# Seeeduino_Stalker_v3_1.net
KiCad netlist of a schematic drawn in EAGLE
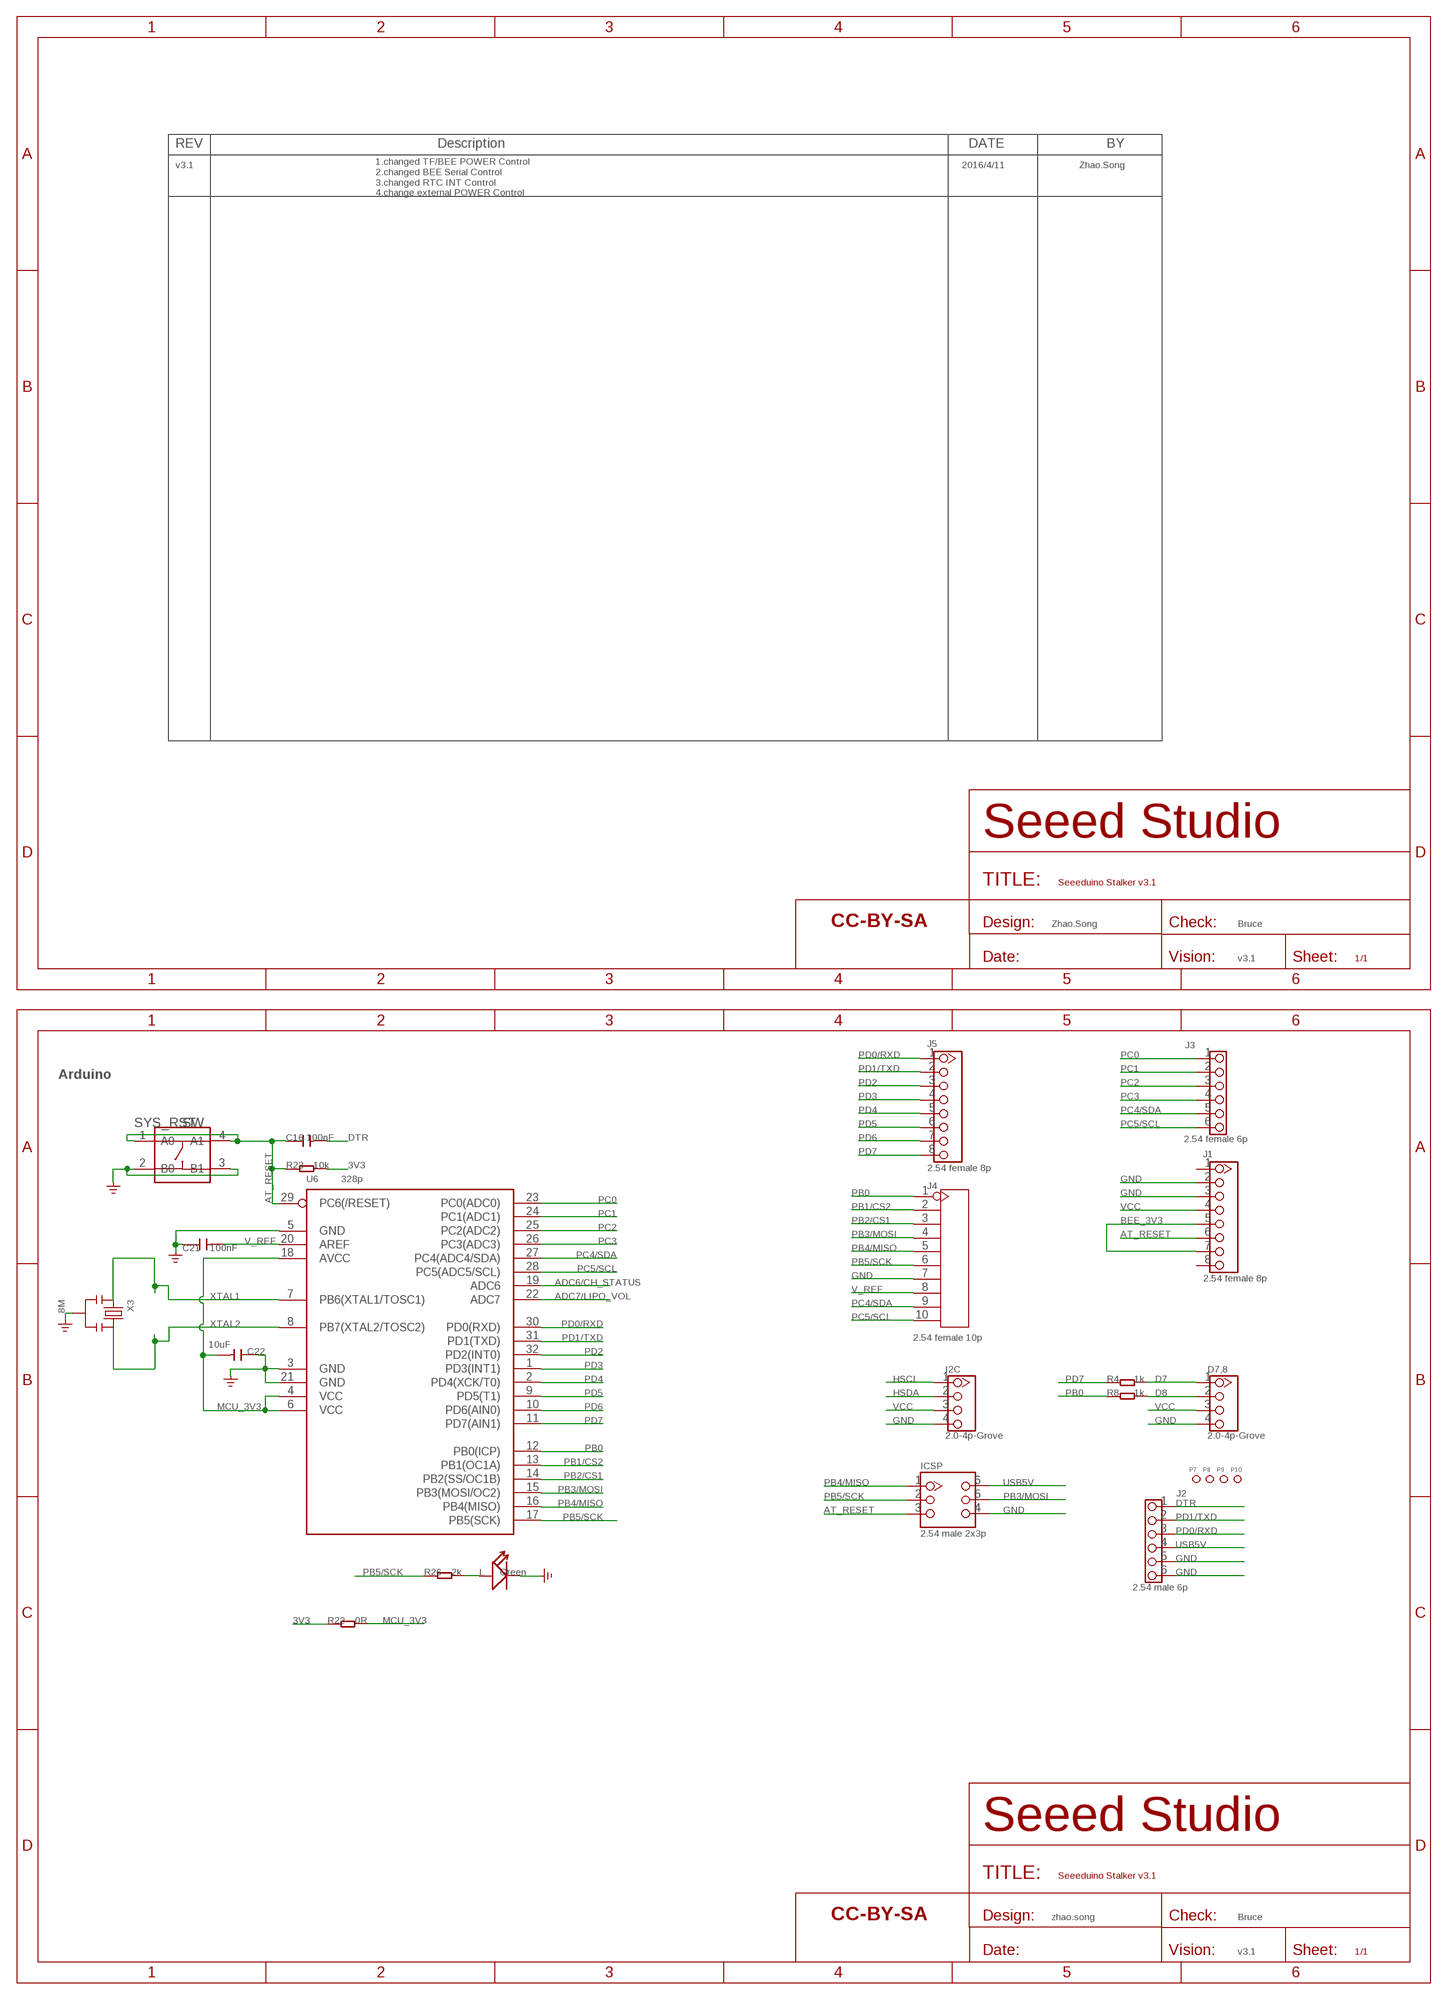
[diagram p0: schematic, sheet 1, part 1 of 2]
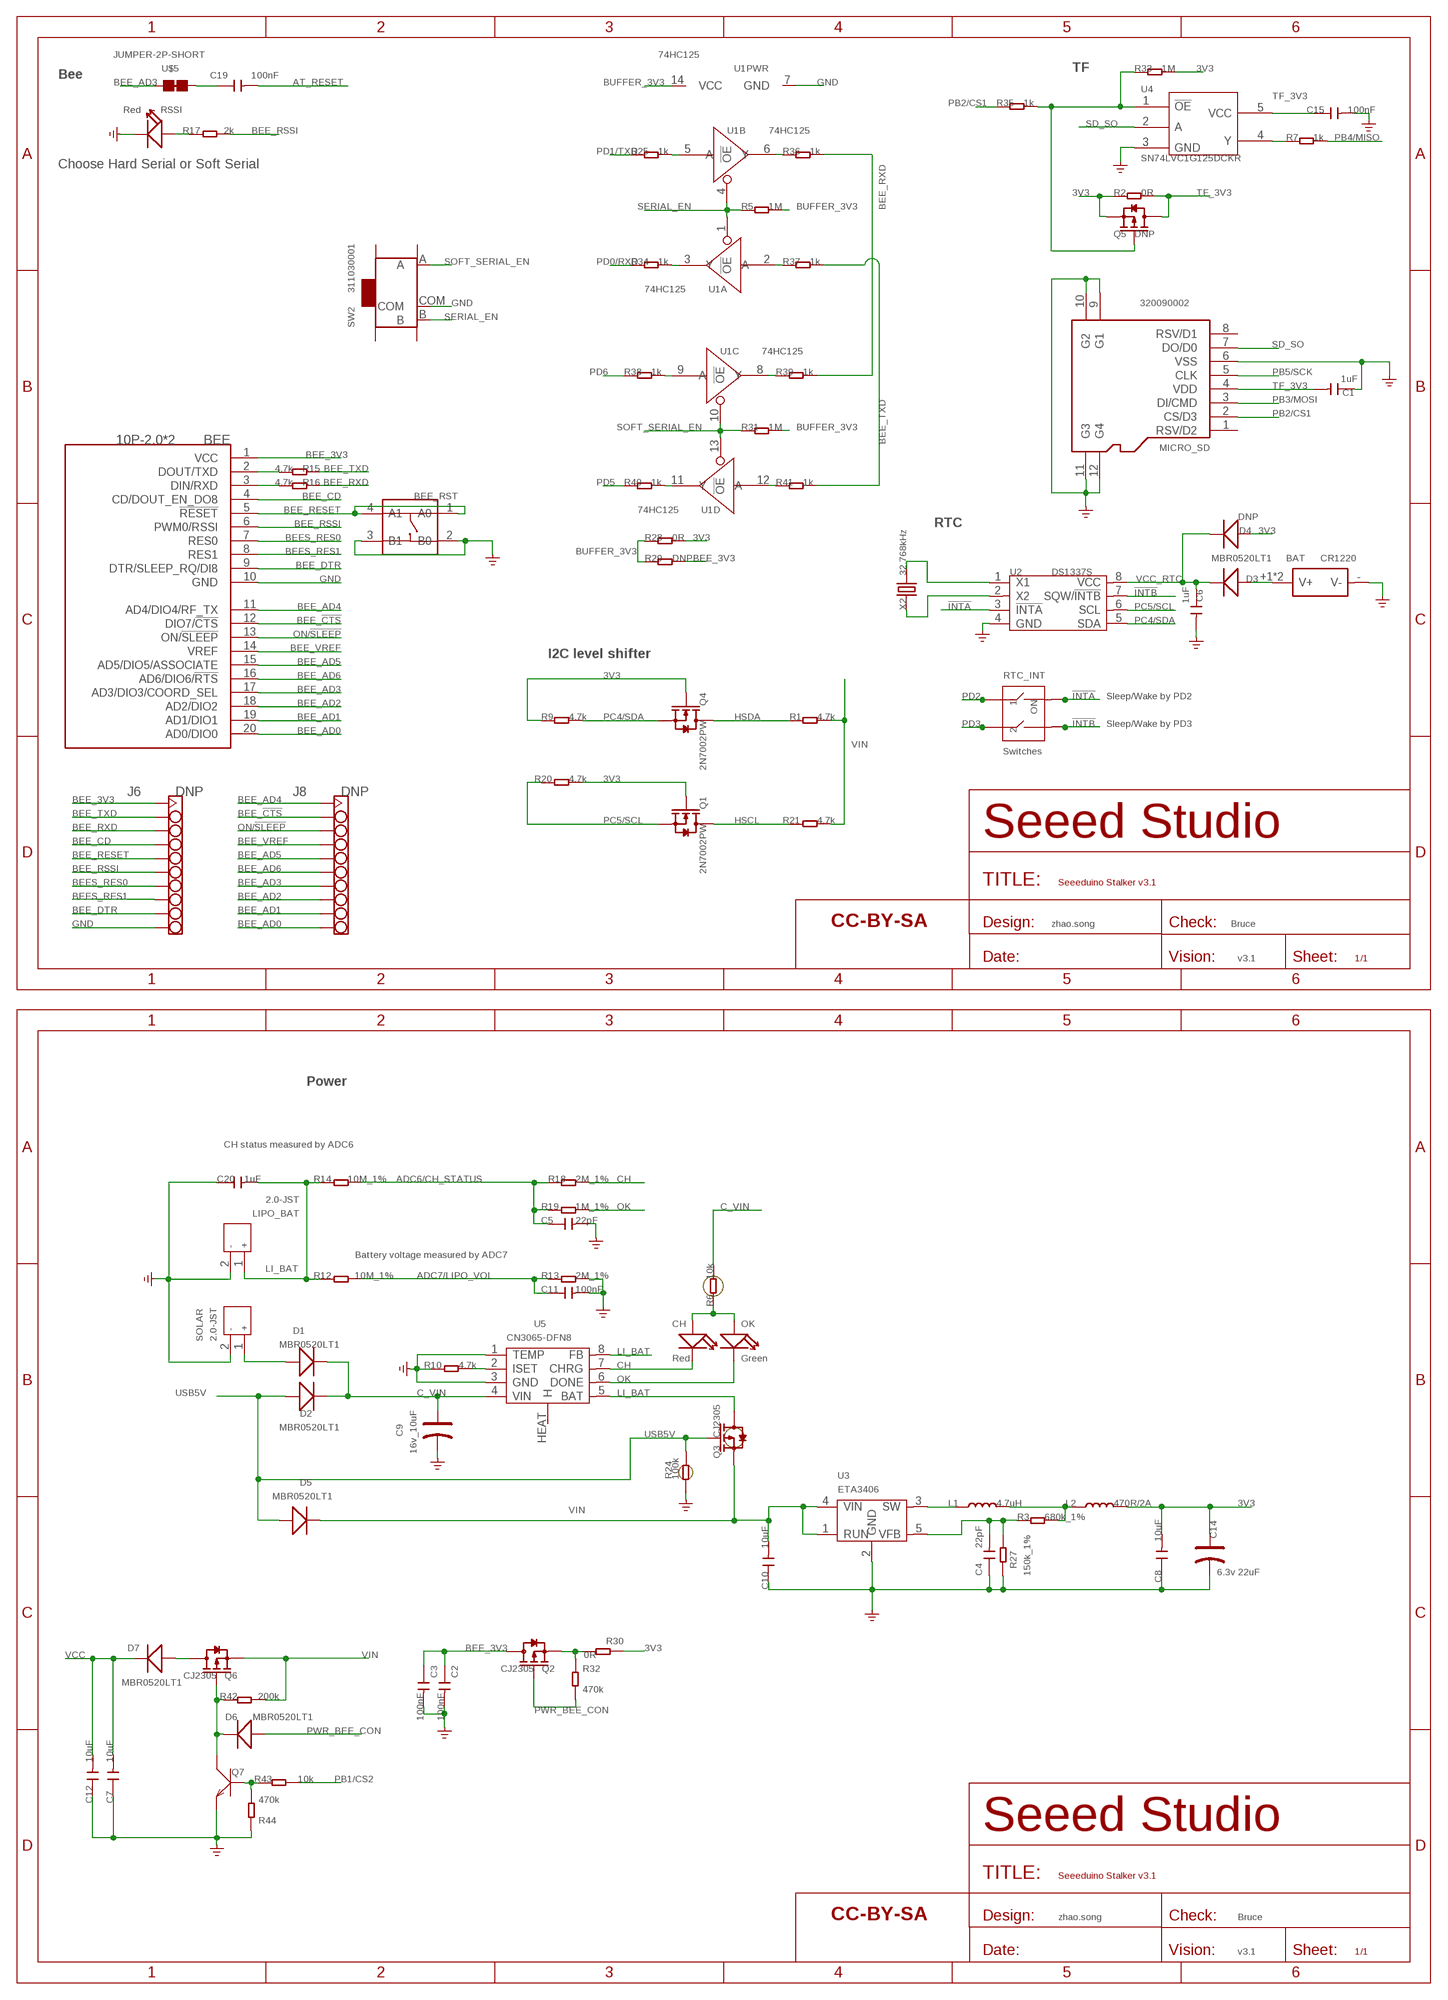
[diagram p1: schematic, sheet 1, part 2 of 2]

(export (version "E")
  (design (tool "Eeschema 10.0.6"))
  (components
    (comp (ref "BAT")
      (value "CR1220")
      (footprint "eagle-import:BAT2P-13.5-CR1220")
      (libsource (lib "eagle-import") (part "BAT-HOLDER-1220"))
    )
    (comp (ref "BEE")
      (value "10P-2.0*2")
      (footprint "eagle-import:BEE")
      (libsource (lib "eagle-import") (part "BEEO"))
    )
    (comp (ref "BEE_RST")
      (value "SW")
      (footprint "eagle-import:4P-SMD-6.2X6.2X4H")
      (libsource (lib "eagle-import") (part "BUTTON-4P-6X6-SMD"))
    )
    (comp (ref "C1")
      (value "1uF")
      (footprint "eagle-import:C0805")
      (libsource (lib "eagle-import") (part "C-0805"))
    )
    (comp (ref "C2")
      (value "100nF")
      (footprint "eagle-import:C0603")
      (libsource (lib "eagle-import") (part "C-0603"))
    )
    (comp (ref "C3")
      (value "100nF")
      (footprint "eagle-import:C0603")
      (libsource (lib "eagle-import") (part "C-0603"))
    )
    (comp (ref "C4")
      (value "22pF")
      (footprint "eagle-import:C0603")
      (libsource (lib "eagle-import") (part "C-0603"))
    )
    (comp (ref "C5")
      (value "22pF")
      (footprint "eagle-import:C0603")
      (libsource (lib "eagle-import") (part "C-0603"))
    )
    (comp (ref "C6")
      (value "1uF")
      (footprint "eagle-import:C0805")
      (libsource (lib "eagle-import") (part "C-0805"))
    )
    (comp (ref "C7")
      (value "10uF")
      (footprint "eagle-import:C0805")
      (libsource (lib "eagle-import") (part "C-0805"))
    )
    (comp (ref "C8")
      (value "10uF")
      (footprint "eagle-import:C0805")
      (libsource (lib "eagle-import") (part "C-0805"))
    )
    (comp (ref "C9")
      (value "16v_10uF")
      (footprint "eagle-import:AVX-A")
      (libsource (lib "eagle-import") (part "CAP-AVX-A"))
    )
    (comp (ref "C10")
      (value "10uF")
      (footprint "eagle-import:C0805")
      (libsource (lib "eagle-import") (part "C-0805"))
    )
    (comp (ref "C11")
      (value "100nF")
      (footprint "eagle-import:C0603")
      (libsource (lib "eagle-import") (part "C-0603"))
    )
    (comp (ref "C12")
      (value "10uF")
      (footprint "eagle-import:C0805")
      (libsource (lib "eagle-import") (part "C-0805"))
    )
    (comp (ref "C14")
      (value "6.3v 22uF")
      (footprint "eagle-import:AVX-A")
      (libsource (lib "eagle-import") (part "CAP-AVX-A"))
    )
    (comp (ref "C15")
      (value "100nF")
      (footprint "eagle-import:C0603")
      (libsource (lib "eagle-import") (part "C-0603"))
    )
    (comp (ref "C16")
      (value "100nF")
      (footprint "eagle-import:C0603")
      (libsource (lib "eagle-import") (part "C-0603"))
    )
    (comp (ref "C19")
      (value "100nF")
      (footprint "eagle-import:C0603")
      (libsource (lib "eagle-import") (part "C-0603"))
    )
    (comp (ref "C20")
      (value "1uF")
      (footprint "eagle-import:C0805")
      (libsource (lib "eagle-import") (part "C-0805"))
    )
    (comp (ref "C21")
      (value "100nF")
      (footprint "eagle-import:C0603")
      (libsource (lib "eagle-import") (part "C-0603"))
    )
    (comp (ref "C22")
      (value "10uF")
      (footprint "eagle-import:C0805")
      (libsource (lib "eagle-import") (part "C-0805"))
    )
    (comp (ref "CH")
      (value "Red")
      (footprint "eagle-import:D0603")
      (libsource (lib "eagle-import") (part "007-LED0603"))
    )
    (comp (ref "D1")
      (value "MBR0520LT1")
      (footprint "eagle-import:SOD123-2.7X1.6")
      (libsource (lib "eagle-import") (part "D'MBR0520LT1'"))
    )
    (comp (ref "D2")
      (value "MBR0520LT1")
      (footprint "eagle-import:SOD123-2.7X1.6")
      (libsource (lib "eagle-import") (part "D'MBR0520LT1'"))
    )
    (comp (ref "D3")
      (value "MBR0520LT1")
      (footprint "eagle-import:SOD123-2.7X1.6")
      (libsource (lib "eagle-import") (part "D'MBR0520LT1'"))
    )
    (comp (ref "D4")
      (value "DNP")
      (footprint "eagle-import:SOD123-2.7X1.6")
      (libsource (lib "eagle-import") (part "D'MBR0520LT1'"))
    )
    (comp (ref "D5")
      (value "MBR0520LT1")
      (footprint "eagle-import:SOD123-2.7X1.6")
      (libsource (lib "eagle-import") (part "D'MBR0520LT1'"))
    )
    (comp (ref "D6")
      (value "MBR0520LT1")
      (footprint "eagle-import:SOD123-2.7X1.6")
      (libsource (lib "eagle-import") (part "D'MBR0520LT1'"))
    )
    (comp (ref "D7")
      (value "MBR0520LT1")
      (footprint "eagle-import:SOD123-2.7X1.6")
      (libsource (lib "eagle-import") (part "D'MBR0520LT1'"))
    )
    (comp (ref "D7,8")
      (value "2.0-4p-Grove")
      (footprint "eagle-import:4P-2.0")
      (libsource (lib "eagle-import") (part "TWIG-4P-2.0-2.0"))
    )
    (comp (ref "I2C")
      (value "2.0-4p-Grove")
      (footprint "eagle-import:4P-2.0")
      (libsource (lib "eagle-import") (part "TWIG-4P-2.0-2.0"))
    )
    (comp (ref "ICSP")
      (value "2.54 male 2x3p")
      (footprint "eagle-import:2X3P-2.54-LEADED")
      (libsource (lib "eagle-import") (part "HEADER-2X3P-2.54"))
    )
    (comp (ref "J1")
      (value "2.54 female 8p")
      (footprint "eagle-import:8P-2.54-LEADED")
      (libsource (lib "eagle-import") (part "HEADER-8P-2.54-LEADED"))
    )
    (comp (ref "J2")
      (value "2.54 male 6p")
      (footprint "eagle-import:6P-2.54-LEADED")
      (libsource (lib "eagle-import") (part "HEADER-6P-LEADED-2.54"))
    )
    (comp (ref "J3")
      (value "2.54 female 6p")
      (footprint "eagle-import:6P-2.54-LEADED")
      (libsource (lib "eagle-import") (part "HEADER-6P-LEADED-2.54"))
    )
    (comp (ref "J4")
      (value "2.54 female 10p")
      (footprint "eagle-import:10P-2.54")
      (libsource (lib "eagle-import") (part "HEADER-10P-2.54"))
    )
    (comp (ref "J5")
      (value "2.54 female 8p")
      (footprint "eagle-import:8P-2.54-LEADED")
      (libsource (lib "eagle-import") (part "HEADER-8P-2.54-LEADED"))
    )
    (comp (ref "J6")
      (value "DNP")
      (footprint "eagle-import:HEADER_1X10")
      (libsource (lib "eagle-import") (part "HEADER_1X10DD"))
    )
    (comp (ref "J8")
      (value "DNP")
      (footprint "eagle-import:HEADER_1X10")
      (libsource (lib "eagle-import") (part "HEADER_1X10DD"))
    )
    (comp (ref "L")
      (value "Green")
      (footprint "eagle-import:D0603")
      (libsource (lib "eagle-import") (part "007-LED0603"))
    )
    (comp (ref "L1")
      (value "4.7uH")
      (footprint "eagle-import:L0420")
      (libsource (lib "eagle-import") (part "LSPD3D16-4R7M"))
    )
    (comp (ref "L2")
      (value "470R/2A")
      (footprint "eagle-import:L0805")
      (libsource (lib "eagle-import") (part "L'0805'"))
    )
    (comp (ref "LIPO_BAT")
      (value "2.0-JST")
      (footprint "eagle-import:JST-2.0")
      (libsource (lib "eagle-import") (part "JACK-JST-2P-PW'2.0'"))
    )
    (comp (ref "MICRO_SD")
      (value "320090002")
      (footprint "eagle-import:MICRO-SD8+4P-SMD-14.5X13.6X1.8MM")
      (libsource (lib "eagle-import") (part "MICRO-SD-CARD-HOLDER-8P"))
    )
    (comp (ref "OK")
      (value "Green")
      (footprint "eagle-import:D0603")
      (libsource (lib "eagle-import") (part "007-LED0603"))
    )
    (comp (ref "P7")
      (value "DNP")
      (footprint "eagle-import:ROUND-MARK-1.0")
      (libsource (lib "eagle-import") (part "PAD-MARK"))
    )
    (comp (ref "P8")
      (value "DNP")
      (footprint "eagle-import:ROUND-MARK-1.0")
      (libsource (lib "eagle-import") (part "PAD-MARK"))
    )
    (comp (ref "P9")
      (value "DNP")
      (footprint "eagle-import:ROUND-MARK-1.0")
      (libsource (lib "eagle-import") (part "PAD-MARK"))
    )
    (comp (ref "P10")
      (value "DNP")
      (footprint "eagle-import:ROUND-MARK-1.0")
      (libsource (lib "eagle-import") (part "PAD-MARK"))
    )
    (comp (ref "Q1")
      (value "2N7002PW")
      (footprint "eagle-import:SOT23")
      (libsource (lib "eagle-import") (part "MOSFET-N'SOT23'"))
    )
    (comp (ref "Q2")
      (value "CJ2305")
      (footprint "eagle-import:SOT23")
      (libsource (lib "eagle-import") (part "MOSFET-P'SI2323CDS/SI2305DS{lt}BR{gt}'"))
    )
    (comp (ref "Q3")
      (value "CJ2305")
      (footprint "eagle-import:SOT23")
      (libsource (lib "eagle-import") (part "MOSFET-P'SI2323CDS/SI2305DS{lt}BR{gt}'"))
    )
    (comp (ref "Q4")
      (value "2N7002PW")
      (footprint "eagle-import:SOT23")
      (libsource (lib "eagle-import") (part "MOSFET-N'SOT23'"))
    )
    (comp (ref "Q5")
      (value "DNP")
      (footprint "eagle-import:SOT23")
      (libsource (lib "eagle-import") (part "MOSFET-P'SI2323CDS/SI2305DS{lt}BR{gt}'"))
    )
    (comp (ref "Q6")
      (value "CJ2305")
      (footprint "eagle-import:SOT23")
      (libsource (lib "eagle-import") (part "MOSFET-P'SI2323CDS/SI2305DS{lt}BR{gt}'"))
    )
    (comp (ref "Q7")
      (value "TRANSISTOR-NPN-SOT23")
      (footprint "eagle-import:SOT-23")
      (libsource (lib "eagle-import") (part "TRANSISTOR-NPN-SOT23"))
    )
    (comp (ref "R1")
      (value "4.7k")
      (footprint "eagle-import:0603@1")
      (libsource (lib "eagle-import") (part "005-R0603"))
    )
    (comp (ref "R2")
      (value "0R")
      (footprint "eagle-import:0603@1")
      (libsource (lib "eagle-import") (part "005-R0603"))
    )
    (comp (ref "R3")
      (value "680k_1%")
      (footprint "eagle-import:0603@1")
      (libsource (lib "eagle-import") (part "005-R0603"))
    )
    (comp (ref "R4")
      (value "1k")
      (footprint "eagle-import:0603@1")
      (libsource (lib "eagle-import") (part "005-R0603"))
    )
    (comp (ref "R5")
      (value "1M")
      (footprint "eagle-import:0603@1")
      (libsource (lib "eagle-import") (part "005-R0603"))
    )
    (comp (ref "R6")
      (value "10k")
      (footprint "eagle-import:0603@1")
      (libsource (lib "eagle-import") (part "005-R0603"))
    )
    (comp (ref "R7")
      (value "1k")
      (footprint "eagle-import:0603@1")
      (libsource (lib "eagle-import") (part "005-R0603"))
    )
    (comp (ref "R8")
      (value "1k")
      (footprint "eagle-import:0603@1")
      (libsource (lib "eagle-import") (part "005-R0603"))
    )
    (comp (ref "R9")
      (value "4.7k")
      (footprint "eagle-import:0603@1")
      (libsource (lib "eagle-import") (part "005-R0603"))
    )
    (comp (ref "R10")
      (value "4.7k")
      (footprint "eagle-import:0603@1")
      (libsource (lib "eagle-import") (part "005-R0603"))
    )
    (comp (ref "R12")
      (value "10M_1%")
      (footprint "eagle-import:0603@1")
      (libsource (lib "eagle-import") (part "005-R0603"))
    )
    (comp (ref "R13")
      (value "2M_1%")
      (footprint "eagle-import:0603@1")
      (libsource (lib "eagle-import") (part "005-R0603"))
    )
    (comp (ref "R14")
      (value "10M_1%")
      (footprint "eagle-import:0603@1")
      (libsource (lib "eagle-import") (part "005-R0603"))
    )
    (comp (ref "R15")
      (value "4.7k")
      (footprint "eagle-import:0603@1")
      (libsource (lib "eagle-import") (part "005-R0603"))
    )
    (comp (ref "R16")
      (value "4.7k")
      (footprint "eagle-import:0603@1")
      (libsource (lib "eagle-import") (part "005-R0603"))
    )
    (comp (ref "R17")
      (value "2k")
      (footprint "eagle-import:0603@1")
      (libsource (lib "eagle-import") (part "005-R0603"))
    )
    (comp (ref "R18")
      (value "2M_1%")
      (footprint "eagle-import:0603@1")
      (libsource (lib "eagle-import") (part "005-R0603"))
    )
    (comp (ref "R19")
      (value "1M_1%")
      (footprint "eagle-import:0603@1")
      (libsource (lib "eagle-import") (part "005-R0603"))
    )
    (comp (ref "R20")
      (value "4.7k")
      (footprint "eagle-import:0603@1")
      (libsource (lib "eagle-import") (part "005-R0603"))
    )
    (comp (ref "R21")
      (value "4.7k")
      (footprint "eagle-import:0603@1")
      (libsource (lib "eagle-import") (part "005-R0603"))
    )
    (comp (ref "R22")
      (value "0R")
      (footprint "eagle-import:0603@1")
      (libsource (lib "eagle-import") (part "005-R0603"))
    )
    (comp (ref "R23")
      (value "10k")
      (footprint "eagle-import:0603@1")
      (libsource (lib "eagle-import") (part "005-R0603"))
    )
    (comp (ref "R24")
      (value "100k")
      (footprint "eagle-import:0603@1")
      (libsource (lib "eagle-import") (part "005-R0603"))
    )
    (comp (ref "R25")
      (value "1k")
      (footprint "eagle-import:0603@1")
      (libsource (lib "eagle-import") (part "005-R0603"))
    )
    (comp (ref "R26")
      (value "2k")
      (footprint "eagle-import:0603@1")
      (libsource (lib "eagle-import") (part "005-R0603"))
    )
    (comp (ref "R27")
      (value "150k_1%")
      (footprint "eagle-import:0603@1")
      (libsource (lib "eagle-import") (part "005-R0603"))
    )
    (comp (ref "R28")
      (value "0R")
      (footprint "eagle-import:0603@1")
      (libsource (lib "eagle-import") (part "005-R0603"))
    )
    (comp (ref "R29")
      (value "DNP")
      (footprint "eagle-import:0603@1")
      (libsource (lib "eagle-import") (part "005-R0603"))
    )
    (comp (ref "R30")
      (value "0R")
      (footprint "eagle-import:0603@1")
      (libsource (lib "eagle-import") (part "005-R0603"))
    )
    (comp (ref "R31")
      (value "1M")
      (footprint "eagle-import:0603@1")
      (libsource (lib "eagle-import") (part "005-R0603"))
    )
    (comp (ref "R32")
      (value "470k")
      (footprint "eagle-import:0603@1")
      (libsource (lib "eagle-import") (part "005-R0603"))
    )
    (comp (ref "R33")
      (value "1M")
      (footprint "eagle-import:0603@1")
      (libsource (lib "eagle-import") (part "005-R0603"))
    )
    (comp (ref "R34")
      (value "1k")
      (footprint "eagle-import:0603@1")
      (libsource (lib "eagle-import") (part "005-R0603"))
    )
    (comp (ref "R35")
      (value "1k")
      (footprint "eagle-import:0603@1")
      (libsource (lib "eagle-import") (part "005-R0603"))
    )
    (comp (ref "R36")
      (value "1k")
      (footprint "eagle-import:0603@1")
      (libsource (lib "eagle-import") (part "005-R0603"))
    )
    (comp (ref "R37")
      (value "1k")
      (footprint "eagle-import:0603@1")
      (libsource (lib "eagle-import") (part "005-R0603"))
    )
    (comp (ref "R38")
      (value "1k")
      (footprint "eagle-import:0603@1")
      (libsource (lib "eagle-import") (part "005-R0603"))
    )
    (comp (ref "R39")
      (value "1k")
      (footprint "eagle-import:0603@1")
      (libsource (lib "eagle-import") (part "005-R0603"))
    )
    (comp (ref "R40")
      (value "1k")
      (footprint "eagle-import:0603@1")
      (libsource (lib "eagle-import") (part "005-R0603"))
    )
    (comp (ref "R41")
      (value "1k")
      (footprint "eagle-import:0603@1")
      (libsource (lib "eagle-import") (part "005-R0603"))
    )
    (comp (ref "R42")
      (value "200k")
      (footprint "eagle-import:0603@1")
      (libsource (lib "eagle-import") (part "005-R0603"))
    )
    (comp (ref "R43")
      (value "10k")
      (footprint "eagle-import:0603@1")
      (libsource (lib "eagle-import") (part "005-R0603"))
    )
    (comp (ref "R44")
      (value "470k")
      (footprint "eagle-import:0603@1")
      (libsource (lib "eagle-import") (part "005-R0603"))
    )
    (comp (ref "RSSI")
      (value "Red")
      (footprint "eagle-import:D0603")
      (libsource (lib "eagle-import") (part "007-LED0603"))
    )
    (comp (ref "RTC_INT")
      (value "Switches")
      (footprint "eagle-import:SW4-SMD-2.54-5.08X6.8X3.3MM")
      (libsource (lib "eagle-import") (part "SWITCHES-2X2P'KM-02'"))
    )
    (comp (ref "SOLAR")
      (value "2.0-JST")
      (footprint "eagle-import:JST-2.0")
      (libsource (lib "eagle-import") (part "JACK-JST-2P-PW'2.0'"))
    )
    (comp (ref "SW2")
      (value "311030001")
      (footprint "eagle-import:SW7-SMD-L6.7X2.7X3.2MM")
      (libsource (lib "eagle-import") (part "SWITCH-3+4P"))
    )
    (comp (ref "SYS_RST")
      (value "SW")
      (footprint "eagle-import:4P-SMD-6.2X6.2X4H")
      (libsource (lib "eagle-import") (part "BUTTON-4P-6X6-SMD"))
    )
    (comp (ref "U$2")
      (value "DNP")
      (footprint "eagle-import:SEEEDSTUDIO-PCB-FRAME")
      (libsource (lib "eagle-import") (part "SEEEDSTUDIO-OPEN-SCH-FRAME"))
    )
    (comp (ref "U$5")
      (value "JUMPER-2P-SHORT")
      (footprint "eagle-import:2P-SMD-SHORT")
      (libsource (lib "eagle-import") (part "JUMPER-2P-SHORT"))
    )
    (comp (ref "U$11")
      (value "DNP")
      (footprint "eagle-import:SEEEDSTUDIO-PCB-FRAME")
      (libsource (lib "eagle-import") (part "SEEEDSTUDIO-OPEN-SCH-FRAME"))
    )
    (comp (ref "U$12")
      (value "DNP")
      (footprint "eagle-import:SEEEDSTUDIO-PCB-FRAME")
      (libsource (lib "eagle-import") (part "SEEEDSTUDIO-OPEN-SCH-FRAME"))
    )
    (comp (ref "U$27")
      (value "DNP")
      (footprint "eagle-import:SEEEDSTUDIO-PCB-FRAME")
      (libsource (lib "eagle-import") (part "SEEEDSTUDIO-OPEN-SCH-FRAME"))
    )
    (comp (ref "U1")
      (value "74HC125")
      (footprint "eagle-import:TSSOP14-0.65-5X4.4MM")
      (libsource (lib "eagle-import") (part "LOGIC-74125PWHCT"))
    )
    (comp (ref "U2")
      (value "DS1337S")
      (footprint "eagle-import:SOP8")
      (libsource (lib "eagle-import") (part "DS1337S"))
    )
    (comp (ref "U3")
      (value "ETA3406")
      (footprint "eagle-import:SOT23-5")
      (libsource (lib "eagle-import") (part "TD6810'TSOT23-5'"))
    )
    (comp (ref "U4")
      (value "SN74LVC1G125DCKR")
      (footprint "eagle-import:SOT353")
      (libsource (lib "eagle-import") (part "SN74LVC1G125DCKR"))
    )
    (comp (ref "U5")
      (value "CN3065-DFN8")
      (footprint "eagle-import:DFN8")
      (libsource (lib "eagle-import") (part "CN3065-DFN8"))
    )
    (comp (ref "U6")
      (value "328p")
      (footprint "eagle-import:TQFP32-0.8-7X7MM")
      (libsource (lib "eagle-import") (part "MCU-ATMEGA8/168/328'AU'"))
    )
    (comp (ref "X2")
      (value "32.768kHz")
      (footprint "eagle-import:2P-SMD-3.2X1.5")
      (libsource (lib "eagle-import") (part "CRYSTAL-3215"))
    )
    (comp (ref "X3")
      (value "8M")
      (footprint "eagle-import:RESONATOR3-SMD-3.6X1.3X0.8MM")
      (libsource (lib "eagle-import") (part "CRYSTAL-RESONATOR'SMD'"))
    )
  )
  (nets
    (net (code "1") (name "/3V3") (class "Default")
      (node (ref "C14") (pin "+") (pinfunction "+_+") (pintype "passive"))
      (node (ref "C8") (pin "2") (pinfunction "2_2") (pintype "passive"))
      (node (ref "D4") (pin "1") (pinfunction "+_1") (pintype "passive"))
      (node (ref "L2") (pin "2") (pinfunction "2_2") (pintype "passive"))
      (node (ref "Q1") (pin "1") (pinfunction "G_1") (pintype "passive"))
      (node (ref "Q4") (pin "1") (pinfunction "G_1") (pintype "passive"))
      (node (ref "Q5") (pin "2") (pinfunction "S_2") (pintype "passive"))
      (node (ref "R2") (pin "1") (pinfunction "1_1") (pintype "passive"))
      (node (ref "R20") (pin "2") (pinfunction "2_2") (pintype "passive"))
      (node (ref "R22") (pin "1") (pinfunction "1_1") (pintype "passive"))
      (node (ref "R23") (pin "2") (pinfunction "2_2") (pintype "passive"))
      (node (ref "R28") (pin "2") (pinfunction "2_2") (pintype "passive"))
      (node (ref "R30") (pin "1") (pinfunction "1_1") (pintype "passive"))
      (node (ref "R33") (pin "2") (pinfunction "2_2") (pintype "passive"))
      (node (ref "R9") (pin "1") (pinfunction "1_1") (pintype "passive"))
    )
    (net (code "2") (name "/ADC6{slash}CH_STATUS") (class "Default")
      (node (ref "C5") (pin "1") (pinfunction "1_1") (pintype "passive"))
      (node (ref "R14") (pin "2") (pinfunction "2_2") (pintype "passive"))
      (node (ref "R18") (pin "1") (pinfunction "1_1") (pintype "passive"))
      (node (ref "R19") (pin "1") (pinfunction "1_1") (pintype "passive"))
      (node (ref "U6") (pin "19") (pinfunction "ADC6_19") (pintype "bidirectional"))
    )
    (net (code "3") (name "/ADC7{slash}LIPO_VOL") (class "Default")
      (node (ref "C11") (pin "1") (pinfunction "1_1") (pintype "passive"))
      (node (ref "R12") (pin "2") (pinfunction "2_2") (pintype "passive"))
      (node (ref "R13") (pin "1") (pinfunction "1_1") (pintype "passive"))
      (node (ref "U6") (pin "22") (pinfunction "ADC7_22") (pintype "bidirectional"))
    )
    (net (code "4") (name "/AT_RESET") (class "Default")
      (node (ref "C16") (pin "1") (pinfunction "1_1") (pintype "passive"))
      (node (ref "C19") (pin "2") (pinfunction "2_2") (pintype "passive"))
      (node (ref "ICSP") (pin "3") (pinfunction "3_3") (pintype "bidirectional"))
      (node (ref "J1") (pin "6") (pinfunction "6_6") (pintype "bidirectional"))
      (node (ref "R23") (pin "1") (pinfunction "1_1") (pintype "passive"))
      (node (ref "SYS_RST") (pin "1") (pinfunction "A0_1") (pintype "bidirectional"))
      (node (ref "SYS_RST") (pin "4") (pinfunction "A1_4") (pintype "bidirectional"))
      (node (ref "U6") (pin "29") (pinfunction "PC6(/RESET)_29") (pintype "bidirectional"))
    )
    (net (code "5") (name "/BEES_RES0") (class "Default")
      (node (ref "BEE") (pin "7") (pinfunction "RES0_7") (pintype "bidirectional"))
      (node (ref "J6") (pin "7") (pinfunction "7_7") (pintype "bidirectional"))
    )
    (net (code "6") (name "/BEES_RES1") (class "Default")
      (node (ref "BEE") (pin "8") (pinfunction "RES1_8") (pintype "bidirectional"))
      (node (ref "J6") (pin "8") (pinfunction "8_8") (pintype "bidirectional"))
    )
    (net (code "7") (name "/BEE_3V3") (class "Default")
      (node (ref "BEE") (pin "1") (pinfunction "VCC_1") (pintype "bidirectional"))
      (node (ref "C2") (pin "1") (pinfunction "1_1") (pintype "passive"))
      (node (ref "C3") (pin "1") (pinfunction "1_1") (pintype "passive"))
      (node (ref "J1") (pin "5") (pinfunction "5_5") (pintype "bidirectional"))
      (node (ref "J1") (pin "7") (pinfunction "7_7") (pintype "bidirectional"))
      (node (ref "J6") (pin "1") (pinfunction "1_1") (pintype "bidirectional"))
      (node (ref "Q2") (pin "3") (pinfunction "D_3") (pintype "passive"))
      (node (ref "R29") (pin "2") (pinfunction "2_2") (pintype "passive"))
    )
    (net (code "8") (name "/BEE_AD0") (class "Default")
      (node (ref "BEE") (pin "20") (pinfunction "AD0/DIO0_20") (pintype "bidirectional"))
      (node (ref "J8") (pin "10") (pinfunction "10_10") (pintype "bidirectional"))
    )
    (net (code "9") (name "/BEE_AD1") (class "Default")
      (node (ref "BEE") (pin "19") (pinfunction "AD1/DIO1_19") (pintype "bidirectional"))
      (node (ref "J8") (pin "9") (pinfunction "9_9") (pintype "bidirectional"))
    )
    (net (code "10") (name "/BEE_AD2") (class "Default")
      (node (ref "BEE") (pin "18") (pinfunction "AD2/DIO2_18") (pintype "bidirectional"))
      (node (ref "J8") (pin "8") (pinfunction "8_8") (pintype "bidirectional"))
    )
    (net (code "11") (name "/BEE_AD3") (class "Default")
      (node (ref "BEE") (pin "17") (pinfunction "AD3/DIO3/COORD_SEL_17") (pintype "bidirectional"))
      (node (ref "J8") (pin "7") (pinfunction "7_7") (pintype "bidirectional"))
      (node (ref "U$5") (pin "1") (pinfunction "1_1") (pintype "bidirectional"))
    )
    (net (code "12") (name "/BEE_AD4") (class "Default")
      (node (ref "BEE") (pin "11") (pinfunction "AD4/DIO4/RF_TX_11") (pintype "bidirectional"))
      (node (ref "J8") (pin "1") (pinfunction "1_1") (pintype "bidirectional"))
    )
    (net (code "13") (name "/BEE_AD5") (class "Default")
      (node (ref "BEE") (pin "15") (pinfunction "AD5/DIO5/ASSOCIATE_15") (pintype "bidirectional"))
      (node (ref "J8") (pin "5") (pinfunction "5_5") (pintype "bidirectional"))
    )
    (net (code "14") (name "/BEE_AD6") (class "Default")
      (node (ref "BEE") (pin "16") (pinfunction "AD6/DIO6/~{RTS}_16") (pintype "bidirectional"))
      (node (ref "J8") (pin "6") (pinfunction "6_6") (pintype "bidirectional"))
    )
    (net (code "15") (name "/BEE_CD") (class "Default")
      (node (ref "BEE") (pin "4") (pinfunction "CD/DOUT_EN_DO8_4") (pintype "bidirectional"))
      (node (ref "J6") (pin "4") (pinfunction "4_4") (pintype "bidirectional"))
    )
    (net (code "16") (name "/BEE_DTR") (class "Default")
      (node (ref "BEE") (pin "9") (pinfunction "DTR/SLEEP_RQ/DI8_9") (pintype "bidirectional"))
      (node (ref "J6") (pin "9") (pinfunction "9_9") (pintype "bidirectional"))
    )
    (net (code "17") (name "/BEE_RESET") (class "Default")
      (node (ref "BEE") (pin "5") (pinfunction "~{RESET}_5") (pintype "bidirectional"))
      (node (ref "BEE_RST") (pin "1") (pinfunction "A0_1") (pintype "bidirectional"))
      (node (ref "BEE_RST") (pin "4") (pinfunction "A1_4") (pintype "bidirectional"))
      (node (ref "J6") (pin "5") (pinfunction "5_5") (pintype "bidirectional"))
    )
    (net (code "18") (name "/BEE_RSSI") (class "Default")
      (node (ref "BEE") (pin "6") (pinfunction "PWM0/RSSI_6") (pintype "bidirectional"))
      (node (ref "J6") (pin "6") (pinfunction "6_6") (pintype "bidirectional"))
      (node (ref "R17") (pin "2") (pinfunction "2_2") (pintype "passive"))
    )
    (net (code "19") (name "/BEE_RXD") (class "Default")
      (node (ref "J6") (pin "3") (pinfunction "3_3") (pintype "bidirectional"))
      (node (ref "R16") (pin "1") (pinfunction "1_1") (pintype "passive"))
      (node (ref "R36") (pin "2") (pinfunction "2_2") (pintype "passive"))
      (node (ref "R39") (pin "2") (pinfunction "2_2") (pintype "passive"))
    )
    (net (code "20") (name "/BEE_TXD") (class "Default")
      (node (ref "J6") (pin "2") (pinfunction "2_2") (pintype "bidirectional"))
      (node (ref "R15") (pin "1") (pinfunction "1_1") (pintype "passive"))
      (node (ref "R37") (pin "2") (pinfunction "2_2") (pintype "passive"))
      (node (ref "R41") (pin "2") (pinfunction "2_2") (pintype "passive"))
    )
    (net (code "21") (name "/BEE_VREF") (class "Default")
      (node (ref "BEE") (pin "14") (pinfunction "VREF_14") (pintype "bidirectional"))
      (node (ref "J8") (pin "4") (pinfunction "4_4") (pintype "bidirectional"))
    )
    (net (code "22") (name "/BEE_~{CTS}") (class "Default")
      (node (ref "BEE") (pin "12") (pinfunction "DIO7/~{CTS}_12") (pintype "bidirectional"))
      (node (ref "J8") (pin "2") (pinfunction "2_2") (pintype "bidirectional"))
    )
    (net (code "23") (name "/BUFFER_3V3") (class "Default")
      (node (ref "R28") (pin "1") (pinfunction "1_1") (pintype "passive"))
      (node (ref "R29") (pin "1") (pinfunction "1_1") (pintype "passive"))
      (node (ref "R31") (pin "2") (pinfunction "2_2") (pintype "passive"))
      (node (ref "R5") (pin "2") (pinfunction "2_2") (pintype "passive"))
      (node (ref "U1") (pin "14") (pinfunction "VCC_14") (pintype "power_in"))
    )
    (net (code "24") (name "/CH") (class "Default")
      (node (ref "CH") (pin "-") (pinfunction "-_-") (pintype "passive"))
      (node (ref "R18") (pin "2") (pinfunction "2_2") (pintype "passive"))
      (node (ref "U5") (pin "7") (pinfunction "CHRG_7") (pintype "bidirectional"))
    )
    (net (code "25") (name "/C_VIN") (class "Default")
      (node (ref "C9") (pin "+") (pinfunction "+_+") (pintype "passive"))
      (node (ref "D1") (pin "2") (pinfunction "-_2") (pintype "passive"))
      (node (ref "D2") (pin "2") (pinfunction "-_2") (pintype "passive"))
      (node (ref "R6") (pin "2") (pinfunction "2_2") (pintype "passive"))
      (node (ref "U5") (pin "4") (pinfunction "VIN_4") (pintype "input"))
    )
    (net (code "26") (name "/D7") (class "Default")
      (node (ref "D7,8") (pin "1") (pinfunction "1_1") (pintype "bidirectional"))
      (node (ref "R4") (pin "2") (pinfunction "2_2") (pintype "passive"))
    )
    (net (code "27") (name "/D8") (class "Default")
      (node (ref "D7,8") (pin "2") (pinfunction "2_2") (pintype "bidirectional"))
      (node (ref "R8") (pin "2") (pinfunction "2_2") (pintype "passive"))
    )
    (net (code "28") (name "/DTR") (class "Default")
      (node (ref "C16") (pin "2") (pinfunction "2_2") (pintype "passive"))
      (node (ref "J2") (pin "1") (pinfunction "1_1") (pintype "bidirectional"))
    )
    (net (code "29") (name "/HSCL") (class "Default")
      (node (ref "I2C") (pin "1") (pinfunction "1_1") (pintype "bidirectional"))
      (node (ref "Q1") (pin "3") (pinfunction "D_3") (pintype "passive"))
      (node (ref "R21") (pin "1") (pinfunction "1_1") (pintype "passive"))
    )
    (net (code "30") (name "/HSDA") (class "Default")
      (node (ref "I2C") (pin "2") (pinfunction "2_2") (pintype "bidirectional"))
      (node (ref "Q4") (pin "3") (pinfunction "D_3") (pintype "passive"))
      (node (ref "R1") (pin "1") (pinfunction "1_1") (pintype "passive"))
    )
    (net (code "31") (name "/LI_BAT") (class "Default")
      (node (ref "C20") (pin "2") (pinfunction "2_2") (pintype "passive"))
      (node (ref "LIPO_BAT") (pin "1") (pinfunction "P$1_1") (pintype "bidirectional"))
      (node (ref "Q3") (pin "3") (pinfunction "D_3") (pintype "passive"))
      (node (ref "R12") (pin "1") (pinfunction "1_1") (pintype "passive"))
      (node (ref "R14") (pin "1") (pinfunction "1_1") (pintype "passive"))
      (node (ref "U5") (pin "5") (pinfunction "BAT_5") (pintype "bidirectional"))
      (node (ref "U5") (pin "8") (pinfunction "FB_8") (pintype "input"))
    )
    (net (code "32") (name "/MCU_3V3") (class "Default")
      (node (ref "C22") (pin "2") (pinfunction "2_2") (pintype "passive"))
      (node (ref "R22") (pin "2") (pinfunction "2_2") (pintype "passive"))
      (node (ref "U6") (pin "18") (pinfunction "AVCC_18") (pintype "bidirectional"))
      (node (ref "U6") (pin "4") (pinfunction "VCC_4") (pintype "bidirectional"))
      (node (ref "U6") (pin "6") (pinfunction "VCC_6") (pintype "bidirectional"))
    )
    (net (code "33") (name "/OK") (class "Default")
      (node (ref "OK") (pin "-") (pinfunction "-_-") (pintype "passive"))
      (node (ref "R19") (pin "2") (pinfunction "2_2") (pintype "passive"))
      (node (ref "U5") (pin "6") (pinfunction "DONE_6") (pintype "bidirectional"))
    )
    (net (code "34") (name "/ON{slash}~{SLEEP}") (class "Default")
      (node (ref "BEE") (pin "13") (pinfunction "ON/~{SLEEP}_13") (pintype "bidirectional"))
      (node (ref "J8") (pin "3") (pinfunction "3_3") (pintype "bidirectional"))
    )
    (net (code "35") (name "/PB0") (class "Default")
      (node (ref "J4") (pin "1") (pinfunction "1_1") (pintype "bidirectional"))
      (node (ref "R8") (pin "1") (pinfunction "1_1") (pintype "passive"))
      (node (ref "U6") (pin "12") (pinfunction "PB0(ICP)_12") (pintype "bidirectional"))
    )
    (net (code "36") (name "/PB1{slash}CS2") (class "Default")
      (node (ref "J4") (pin "2") (pinfunction "2_2") (pintype "bidirectional"))
      (node (ref "R43") (pin "1") (pinfunction "1_1") (pintype "passive"))
      (node (ref "U6") (pin "13") (pinfunction "PB1(OC1A)_13") (pintype "bidirectional"))
    )
    (net (code "37") (name "/PB2{slash}CS1") (class "Default")
      (node (ref "J4") (pin "3") (pinfunction "3_3") (pintype "bidirectional"))
      (node (ref "MICRO_SD") (pin "2") (pinfunction "CS/D3_2") (pintype "bidirectional"))
      (node (ref "R35") (pin "1") (pinfunction "1_1") (pintype "passive"))
      (node (ref "U6") (pin "14") (pinfunction "PB2(SS/OC1B)_14") (pintype "bidirectional"))
    )
    (net (code "38") (name "/PB3{slash}MOSI") (class "Default")
      (node (ref "ICSP") (pin "5") (pinfunction "5_5") (pintype "bidirectional"))
      (node (ref "J4") (pin "4") (pinfunction "4_4") (pintype "bidirectional"))
      (node (ref "MICRO_SD") (pin "3") (pinfunction "DI/CMD_3") (pintype "bidirectional"))
      (node (ref "U6") (pin "15") (pinfunction "PB3(MOSI/OC2)_15") (pintype "bidirectional"))
    )
    (net (code "39") (name "/PB4{slash}MISO") (class "Default")
      (node (ref "ICSP") (pin "1") (pinfunction "1_1") (pintype "bidirectional"))
      (node (ref "J4") (pin "5") (pinfunction "5_5") (pintype "bidirectional"))
      (node (ref "R7") (pin "2") (pinfunction "2_2") (pintype "passive"))
      (node (ref "U6") (pin "16") (pinfunction "PB4(MISO)_16") (pintype "bidirectional"))
    )
    (net (code "40") (name "/PB5{slash}SCK") (class "Default")
      (node (ref "ICSP") (pin "2") (pinfunction "2_2") (pintype "bidirectional"))
      (node (ref "J4") (pin "6") (pinfunction "6_6") (pintype "bidirectional"))
      (node (ref "MICRO_SD") (pin "5") (pinfunction "CLK_5") (pintype "bidirectional"))
      (node (ref "R26") (pin "1") (pinfunction "1_1") (pintype "passive"))
      (node (ref "U6") (pin "17") (pinfunction "PB5(SCK)_17") (pintype "bidirectional"))
    )
    (net (code "41") (name "/PC0") (class "Default")
      (node (ref "J3") (pin "1") (pinfunction "1_1") (pintype "bidirectional"))
      (node (ref "U6") (pin "23") (pinfunction "PC0(ADC0)_23") (pintype "bidirectional"))
    )
    (net (code "42") (name "/PC1") (class "Default")
      (node (ref "J3") (pin "2") (pinfunction "2_2") (pintype "bidirectional"))
      (node (ref "U6") (pin "24") (pinfunction "PC1(ADC1)_24") (pintype "bidirectional"))
    )
    (net (code "43") (name "/PC2") (class "Default")
      (node (ref "J3") (pin "3") (pinfunction "3_3") (pintype "bidirectional"))
      (node (ref "U6") (pin "25") (pinfunction "PC2(ADC2)_25") (pintype "bidirectional"))
    )
    (net (code "44") (name "/PC3") (class "Default")
      (node (ref "J3") (pin "4") (pinfunction "4_4") (pintype "bidirectional"))
      (node (ref "U6") (pin "26") (pinfunction "PC3(ADC3)_26") (pintype "bidirectional"))
    )
    (net (code "45") (name "/PC4{slash}SDA") (class "Default")
      (node (ref "J3") (pin "5") (pinfunction "5_5") (pintype "bidirectional"))
      (node (ref "J4") (pin "9") (pinfunction "9_9") (pintype "bidirectional"))
      (node (ref "Q4") (pin "2") (pinfunction "S_2") (pintype "passive"))
      (node (ref "R9") (pin "2") (pinfunction "2_2") (pintype "passive"))
      (node (ref "U2") (pin "5") (pinfunction "SDA_5") (pintype "bidirectional"))
      (node (ref "U6") (pin "27") (pinfunction "PC4(ADC4/SDA)_27") (pintype "bidirectional"))
    )
    (net (code "46") (name "/PC5{slash}SCL") (class "Default")
      (node (ref "J3") (pin "6") (pinfunction "6_6") (pintype "bidirectional"))
      (node (ref "J4") (pin "10") (pinfunction "10_10") (pintype "bidirectional"))
      (node (ref "Q1") (pin "2") (pinfunction "S_2") (pintype "passive"))
      (node (ref "R20") (pin "1") (pinfunction "1_1") (pintype "passive"))
      (node (ref "U2") (pin "6") (pinfunction "SCL_6") (pintype "bidirectional"))
      (node (ref "U6") (pin "28") (pinfunction "PC5(ADC5/SCL)_28") (pintype "bidirectional"))
    )
    (net (code "47") (name "/PD0{slash}RXD") (class "Default")
      (node (ref "J2") (pin "3") (pinfunction "3_3") (pintype "bidirectional"))
      (node (ref "J5") (pin "1") (pinfunction "1_1") (pintype "bidirectional"))
      (node (ref "R34") (pin "1") (pinfunction "1_1") (pintype "passive"))
      (node (ref "U6") (pin "30") (pinfunction "PD0(RXD)_30") (pintype "bidirectional"))
    )
    (net (code "48") (name "/PD1{slash}TXD") (class "Default")
      (node (ref "J2") (pin "2") (pinfunction "2_2") (pintype "bidirectional"))
      (node (ref "J5") (pin "2") (pinfunction "2_2") (pintype "bidirectional"))
      (node (ref "R25") (pin "1") (pinfunction "1_1") (pintype "passive"))
      (node (ref "U6") (pin "31") (pinfunction "PD1(TXD)_31") (pintype "bidirectional"))
    )
    (net (code "49") (name "/PD2") (class "Default")
      (node (ref "J5") (pin "3") (pinfunction "3_3") (pintype "bidirectional"))
      (node (ref "RTC_INT") (pin "1") (pinfunction "1_1") (pintype "bidirectional"))
      (node (ref "U6") (pin "32") (pinfunction "PD2(INT0)_32") (pintype "bidirectional"))
    )
    (net (code "50") (name "/PD3") (class "Default")
      (node (ref "J5") (pin "4") (pinfunction "4_4") (pintype "bidirectional"))
      (node (ref "RTC_INT") (pin "2") (pinfunction "2_2") (pintype "bidirectional"))
      (node (ref "U6") (pin "1") (pinfunction "PD3(INT1)_1") (pintype "bidirectional"))
    )
    (net (code "51") (name "/PD4") (class "Default")
      (node (ref "J5") (pin "5") (pinfunction "5_5") (pintype "bidirectional"))
      (node (ref "U6") (pin "2") (pinfunction "PD4(XCK/T0)_2") (pintype "bidirectional"))
    )
    (net (code "52") (name "/PD5") (class "Default")
      (node (ref "J5") (pin "6") (pinfunction "6_6") (pintype "bidirectional"))
      (node (ref "R40") (pin "1") (pinfunction "1_1") (pintype "passive"))
      (node (ref "U6") (pin "9") (pinfunction "PD5(T1)_9") (pintype "bidirectional"))
    )
    (net (code "53") (name "/PD6") (class "Default")
      (node (ref "J5") (pin "7") (pinfunction "7_7") (pintype "bidirectional"))
      (node (ref "R38") (pin "1") (pinfunction "1_1") (pintype "passive"))
      (node (ref "U6") (pin "10") (pinfunction "PD6(AIN0)_10") (pintype "bidirectional"))
    )
    (net (code "54") (name "/PD7") (class "Default")
      (node (ref "J5") (pin "8") (pinfunction "8_8") (pintype "bidirectional"))
      (node (ref "R4") (pin "1") (pinfunction "1_1") (pintype "passive"))
      (node (ref "U6") (pin "11") (pinfunction "PD7(AIN1)_11") (pintype "bidirectional"))
    )
    (net (code "55") (name "/PWR_BEE_CON") (class "Default")
      (node (ref "D6") (pin "1") (pinfunction "+_1") (pintype "passive"))
      (node (ref "Q2") (pin "1") (pinfunction "G_1") (pintype "passive"))
      (node (ref "R32") (pin "2") (pinfunction "2_2") (pintype "passive"))
    )
    (net (code "56") (name "/SD_SO") (class "Default")
      (node (ref "MICRO_SD") (pin "7") (pinfunction "DO/D0_7") (pintype "bidirectional"))
      (node (ref "U4") (pin "2") (pinfunction "A_2") (pintype "bidirectional"))
    )
    (net (code "57") (name "/SERIAL_EN") (class "Default")
      (node (ref "R5") (pin "1") (pinfunction "1_1") (pintype "passive"))
      (node (ref "SW2") (pin "B") (pinfunction "B_B") (pintype "bidirectional"))
      (node (ref "U1") (pin "1") (pinfunction "~{OE}_1") (pintype "bidirectional"))
      (node (ref "U1") (pin "4") (pinfunction "~{OE}_4") (pintype "bidirectional"))
    )
    (net (code "58") (name "/SOFT_SERIAL_EN") (class "Default")
      (node (ref "R31") (pin "1") (pinfunction "1_1") (pintype "passive"))
      (node (ref "SW2") (pin "A") (pinfunction "A_A") (pintype "bidirectional"))
      (node (ref "U1") (pin "10") (pinfunction "~{OE}_10") (pintype "bidirectional"))
      (node (ref "U1") (pin "13") (pinfunction "~{OE}_13") (pintype "bidirectional"))
    )
    (net (code "59") (name "/TF_3V3") (class "Default")
      (node (ref "C1") (pin "2") (pinfunction "2_2") (pintype "passive"))
      (node (ref "C15") (pin "1") (pinfunction "1_1") (pintype "passive"))
      (node (ref "MICRO_SD") (pin "4") (pinfunction "VDD_4") (pintype "bidirectional"))
      (node (ref "Q5") (pin "3") (pinfunction "D_3") (pintype "passive"))
      (node (ref "R2") (pin "2") (pinfunction "2_2") (pintype "passive"))
      (node (ref "U4") (pin "5") (pinfunction "VCC_5") (pintype "bidirectional"))
    )
    (net (code "60") (name "/USB5V") (class "Default")
      (node (ref "D2") (pin "1") (pinfunction "+_1") (pintype "passive"))
      (node (ref "D5") (pin "1") (pinfunction "+_1") (pintype "passive"))
      (node (ref "ICSP") (pin "6") (pinfunction "6_6") (pintype "bidirectional"))
      (node (ref "J2") (pin "4") (pinfunction "4_4") (pintype "bidirectional"))
      (node (ref "Q3") (pin "1") (pinfunction "G_1") (pintype "passive"))
      (node (ref "R24") (pin "2") (pinfunction "2_2") (pintype "passive"))
    )
    (net (code "61") (name "/VCC") (class "Default")
      (node (ref "C12") (pin "2") (pinfunction "2_2") (pintype "passive"))
      (node (ref "C7") (pin "2") (pinfunction "2_2") (pintype "passive"))
      (node (ref "D7") (pin "2") (pinfunction "-_2") (pintype "passive"))
      (node (ref "D7,8") (pin "3") (pinfunction "3_3") (pintype "bidirectional"))
      (node (ref "I2C") (pin "3") (pinfunction "3_3") (pintype "bidirectional"))
      (node (ref "J1") (pin "4") (pinfunction "4_4") (pintype "bidirectional"))
    )
    (net (code "62") (name "/VCC_RTC") (class "Default")
      (node (ref "C6") (pin "1") (pinfunction "1_1") (pintype "passive"))
      (node (ref "D3") (pin "2") (pinfunction "-_2") (pintype "passive"))
      (node (ref "D4") (pin "2") (pinfunction "-_2") (pintype "passive"))
      (node (ref "U2") (pin "8") (pinfunction "VCC_8") (pintype "bidirectional"))
    )
    (net (code "63") (name "/VIN") (class "Default")
      (node (ref "C10") (pin "2") (pinfunction "2_2") (pintype "passive"))
      (node (ref "D5") (pin "2") (pinfunction "-_2") (pintype "passive"))
      (node (ref "Q3") (pin "2") (pinfunction "S_2") (pintype "passive"))
      (node (ref "Q6") (pin "2") (pinfunction "S_2") (pintype "passive"))
      (node (ref "R1") (pin "2") (pinfunction "2_2") (pintype "passive"))
      (node (ref "R21") (pin "2") (pinfunction "2_2") (pintype "passive"))
      (node (ref "R42") (pin "1") (pinfunction "1_1") (pintype "passive"))
      (node (ref "U3") (pin "1") (pinfunction "RUN_1") (pintype "bidirectional"))
      (node (ref "U3") (pin "4") (pinfunction "VIN_4") (pintype "input"))
    )
    (net (code "64") (name "/V_REF") (class "Default")
      (node (ref "C21") (pin "2") (pinfunction "2_2") (pintype "passive"))
      (node (ref "J4") (pin "8") (pinfunction "8_8") (pintype "bidirectional"))
      (node (ref "U6") (pin "20") (pinfunction "AREF_20") (pintype "bidirectional"))
    )
    (net (code "65") (name "/XTAL1") (class "Default")
      (node (ref "U6") (pin "7") (pinfunction "PB6(XTAL1/TOSC1)_7") (pintype "bidirectional"))
      (node (ref "X3") (pin "1") (pinfunction "1_1") (pintype "passive"))
    )
    (net (code "66") (name "/XTAL2") (class "Default")
      (node (ref "U6") (pin "8") (pinfunction "PB7(XTAL2/TOSC2)_8") (pintype "bidirectional"))
      (node (ref "X3") (pin "3") (pinfunction "3_3") (pintype "passive"))
    )
    (net (code "67") (name "/~{INTA}") (class "Default")
      (node (ref "RTC_INT") (pin "4") (pinfunction "4_4") (pintype "bidirectional"))
      (node (ref "U2") (pin "3") (pinfunction "~{INTA}_3") (pintype "bidirectional"))
    )
    (net (code "68") (name "/~{INTB}") (class "Default")
      (node (ref "RTC_INT") (pin "3") (pinfunction "3_3") (pintype "bidirectional"))
      (node (ref "U2") (pin "7") (pinfunction "SQW/~{INTB}_7") (pintype "bidirectional"))
    )
    (net (code "69") (name "GND_POWER") (class "Default")
      (node (ref "BAT") (pin "-") (pinfunction "V-_-") (pintype "bidirectional"))
      (node (ref "BEE") (pin "10") (pinfunction "GND_10") (pintype "bidirectional"))
      (node (ref "BEE_RST") (pin "2") (pinfunction "B0_2") (pintype "bidirectional"))
      (node (ref "BEE_RST") (pin "3") (pinfunction "B1_3") (pintype "bidirectional"))
      (node (ref "C1") (pin "1") (pinfunction "1_1") (pintype "passive"))
      (node (ref "C10") (pin "1") (pinfunction "1_1") (pintype "passive"))
      (node (ref "C11") (pin "2") (pinfunction "2_2") (pintype "passive"))
      (node (ref "C12") (pin "1") (pinfunction "1_1") (pintype "passive"))
      (node (ref "C14") (pin "-") (pinfunction "-_-") (pintype "passive"))
      (node (ref "C15") (pin "2") (pinfunction "2_2") (pintype "passive"))
      (node (ref "C2") (pin "2") (pinfunction "2_2") (pintype "passive"))
      (node (ref "C20") (pin "1") (pinfunction "1_1") (pintype "passive"))
      (node (ref "C21") (pin "1") (pinfunction "1_1") (pintype "passive"))
      (node (ref "C22") (pin "1") (pinfunction "1_1") (pintype "passive"))
      (node (ref "C3") (pin "2") (pinfunction "2_2") (pintype "passive"))
      (node (ref "C4") (pin "1") (pinfunction "1_1") (pintype "passive"))
      (node (ref "C5") (pin "2") (pinfunction "2_2") (pintype "passive"))
      (node (ref "C6") (pin "2") (pinfunction "2_2") (pintype "passive"))
      (node (ref "C7") (pin "1") (pinfunction "1_1") (pintype "passive"))
      (node (ref "C8") (pin "1") (pinfunction "1_1") (pintype "passive"))
      (node (ref "C9") (pin "-") (pinfunction "-_-") (pintype "passive"))
      (node (ref "D7,8") (pin "4") (pinfunction "4_4") (pintype "bidirectional"))
      (node (ref "I2C") (pin "4") (pinfunction "4_4") (pintype "bidirectional"))
      (node (ref "ICSP") (pin "4") (pinfunction "4_4") (pintype "bidirectional"))
      (node (ref "J1") (pin "2") (pinfunction "2_2") (pintype "bidirectional"))
      (node (ref "J1") (pin "3") (pinfunction "3_3") (pintype "bidirectional"))
      (node (ref "J2") (pin "5") (pinfunction "5_5") (pintype "bidirectional"))
      (node (ref "J2") (pin "6") (pinfunction "6_6") (pintype "bidirectional"))
      (node (ref "J4") (pin "7") (pinfunction "7_7") (pintype "bidirectional"))
      (node (ref "J6") (pin "10") (pinfunction "10_10") (pintype "bidirectional"))
      (node (ref "L") (pin "-") (pinfunction "-_-") (pintype "passive"))
      (node (ref "LIPO_BAT") (pin "2") (pinfunction "P$2_2") (pintype "bidirectional"))
      (node (ref "MICRO_SD") (pin "10") (pinfunction "G2_10") (pintype "bidirectional"))
      (node (ref "MICRO_SD") (pin "11") (pinfunction "G3_11") (pintype "bidirectional"))
      (node (ref "MICRO_SD") (pin "12") (pinfunction "G4_12") (pintype "bidirectional"))
      (node (ref "MICRO_SD") (pin "6") (pinfunction "VSS_6") (pintype "bidirectional"))
      (node (ref "MICRO_SD") (pin "9") (pinfunction "G1_9") (pintype "bidirectional"))
      (node (ref "Q7") (pin "2") (pinfunction "E_2") (pintype "passive"))
      (node (ref "R10") (pin "1") (pinfunction "1_1") (pintype "passive"))
      (node (ref "R13") (pin "2") (pinfunction "2_2") (pintype "passive"))
      (node (ref "R24") (pin "1") (pinfunction "1_1") (pintype "passive"))
      (node (ref "R27") (pin "1") (pinfunction "1_1") (pintype "passive"))
      (node (ref "R44") (pin "2") (pinfunction "2_2") (pintype "passive"))
      (node (ref "RSSI") (pin "-") (pinfunction "-_-") (pintype "passive"))
      (node (ref "SOLAR") (pin "2") (pinfunction "P$2_2") (pintype "bidirectional"))
      (node (ref "SW2") (pin "COM") (pinfunction "COM_COM") (pintype "bidirectional"))
      (node (ref "SYS_RST") (pin "2") (pinfunction "B0_2") (pintype "bidirectional"))
      (node (ref "SYS_RST") (pin "3") (pinfunction "B1_3") (pintype "bidirectional"))
      (node (ref "U1") (pin "7") (pinfunction "GND_7") (pintype "power_in"))
      (node (ref "U2") (pin "4") (pinfunction "GND_4") (pintype "bidirectional"))
      (node (ref "U3") (pin "2") (pinfunction "GND_2") (pintype "power_in"))
      (node (ref "U4") (pin "3") (pinfunction "GND_3") (pintype "bidirectional"))
      (node (ref "U5") (pin "1") (pinfunction "TEMP_1") (pintype "input"))
      (node (ref "U5") (pin "3") (pinfunction "GND_3") (pintype "power_in"))
      (node (ref "U6") (pin "21") (pinfunction "GND_21") (pintype "bidirectional"))
      (node (ref "U6") (pin "3") (pinfunction "GND_3") (pintype "bidirectional"))
      (node (ref "U6") (pin "5") (pinfunction "GND_5") (pintype "bidirectional"))
      (node (ref "X3") (pin "2") (pinfunction "2_2") (pintype "passive"))
    )
    (net (code "70") (name "Net-(BEE-DIN{slash}RXD)") (class "Default")
      (node (ref "BEE") (pin "3") (pinfunction "DIN/RXD_3") (pintype "bidirectional"))
      (node (ref "R16") (pin "2") (pinfunction "2_2") (pintype "passive"))
    )
    (net (code "71") (name "Net-(BEE-DOUT{slash}TXD)") (class "Default")
      (node (ref "BEE") (pin "2") (pinfunction "DOUT/TXD_2") (pintype "bidirectional"))
      (node (ref "R15") (pin "2") (pinfunction "2_2") (pintype "passive"))
    )
    (net (code "72") (name "Net-(C19-Pad1)") (class "Default")
      (node (ref "C19") (pin "1") (pinfunction "1_1") (pintype "passive"))
      (node (ref "U$5") (pin "2") (pinfunction "2_2") (pintype "bidirectional"))
    )
    (net (code "73") (name "Net-(CH-Pad+)") (class "Default")
      (node (ref "CH") (pin "+") (pinfunction "+_+") (pintype "passive"))
      (node (ref "OK") (pin "+") (pinfunction "+_+") (pintype "passive"))
      (node (ref "R6") (pin "1") (pinfunction "1_1") (pintype "passive"))
    )
    (net (code "74") (name "Net-(D1-+)") (class "Default")
      (node (ref "D1") (pin "1") (pinfunction "+_1") (pintype "passive"))
      (node (ref "SOLAR") (pin "1") (pinfunction "P$1_1") (pintype "bidirectional"))
    )
    (net (code "75") (name "Net-(D3-+)") (class "Default")
      (node (ref "BAT") (pin "+1") (pinfunction "V+_+1") (pintype "bidirectional"))
      (node (ref "BAT") (pin "+2") (pinfunction "V+_+2") (pintype "bidirectional"))
      (node (ref "D3") (pin "1") (pinfunction "+_1") (pintype "passive"))
    )
    (net (code "76") (name "Net-(D6--)") (class "Default")
      (node (ref "D6") (pin "2") (pinfunction "-_2") (pintype "passive"))
      (node (ref "Q6") (pin "1") (pinfunction "G_1") (pintype "passive"))
      (node (ref "Q7") (pin "3") (pinfunction "C_3") (pintype "passive"))
      (node (ref "R42") (pin "2") (pinfunction "2_2") (pintype "passive"))
    )
    (net (code "77") (name "Net-(D7-+)") (class "Default")
      (node (ref "D7") (pin "1") (pinfunction "+_1") (pintype "passive"))
      (node (ref "Q6") (pin "3") (pinfunction "D_3") (pintype "passive"))
    )
    (net (code "78") (name "Net-(L-Pad+)") (class "Default")
      (node (ref "L") (pin "+") (pinfunction "+_+") (pintype "passive"))
      (node (ref "R26") (pin "2") (pinfunction "2_2") (pintype "passive"))
    )
    (net (code "79") (name "Net-(L1-Pad2)") (class "Default")
      (node (ref "L1") (pin "2") (pinfunction "2_2") (pintype "passive"))
      (node (ref "L2") (pin "1") (pinfunction "1_1") (pintype "passive"))
      (node (ref "R3") (pin "2") (pinfunction "2_2") (pintype "passive"))
    )
    (net (code "80") (name "Net-(Q2-S)") (class "Default")
      (node (ref "Q2") (pin "2") (pinfunction "S_2") (pintype "passive"))
      (node (ref "R30") (pin "2") (pinfunction "2_2") (pintype "passive"))
      (node (ref "R32") (pin "1") (pinfunction "1_1") (pintype "passive"))
    )
    (net (code "81") (name "Net-(Q5-G)") (class "Default")
      (node (ref "Q5") (pin "1") (pinfunction "G_1") (pintype "passive"))
      (node (ref "R33") (pin "1") (pinfunction "1_1") (pintype "passive"))
      (node (ref "R35") (pin "2") (pinfunction "2_2") (pintype "passive"))
      (node (ref "U4") (pin "1") (pinfunction "~{OE}_1") (pintype "bidirectional"))
    )
    (net (code "82") (name "Net-(Q7-B)") (class "Default")
      (node (ref "Q7") (pin "1") (pinfunction "B_1") (pintype "passive"))
      (node (ref "R43") (pin "2") (pinfunction "2_2") (pintype "passive"))
      (node (ref "R44") (pin "1") (pinfunction "1_1") (pintype "passive"))
    )
    (net (code "83") (name "Net-(R17-Pad1)") (class "Default")
      (node (ref "R17") (pin "1") (pinfunction "1_1") (pintype "passive"))
      (node (ref "RSSI") (pin "+") (pinfunction "+_+") (pintype "passive"))
    )
    (net (code "84") (name "Net-(U1A-A)") (class "Default")
      (node (ref "R37") (pin "1") (pinfunction "1_1") (pintype "passive"))
      (node (ref "U1") (pin "2") (pinfunction "A_2") (pintype "bidirectional"))
    )
    (net (code "85") (name "Net-(U1A-Y)") (class "Default")
      (node (ref "R34") (pin "2") (pinfunction "2_2") (pintype "passive"))
      (node (ref "U1") (pin "3") (pinfunction "Y_3") (pintype "bidirectional"))
    )
    (net (code "86") (name "Net-(U1B-A)") (class "Default")
      (node (ref "R25") (pin "2") (pinfunction "2_2") (pintype "passive"))
      (node (ref "U1") (pin "5") (pinfunction "A_5") (pintype "bidirectional"))
    )
    (net (code "87") (name "Net-(U1B-Y)") (class "Default")
      (node (ref "R36") (pin "1") (pinfunction "1_1") (pintype "passive"))
      (node (ref "U1") (pin "6") (pinfunction "Y_6") (pintype "bidirectional"))
    )
    (net (code "88") (name "Net-(U1C-A)") (class "Default")
      (node (ref "R38") (pin "2") (pinfunction "2_2") (pintype "passive"))
      (node (ref "U1") (pin "9") (pinfunction "A_9") (pintype "bidirectional"))
    )
    (net (code "89") (name "Net-(U1C-Y)") (class "Default")
      (node (ref "R39") (pin "1") (pinfunction "1_1") (pintype "passive"))
      (node (ref "U1") (pin "8") (pinfunction "Y_8") (pintype "bidirectional"))
    )
    (net (code "90") (name "Net-(U1D-A)") (class "Default")
      (node (ref "R41") (pin "1") (pinfunction "1_1") (pintype "passive"))
      (node (ref "U1") (pin "12") (pinfunction "A_12") (pintype "bidirectional"))
    )
    (net (code "91") (name "Net-(U1D-Y)") (class "Default")
      (node (ref "R40") (pin "2") (pinfunction "2_2") (pintype "passive"))
      (node (ref "U1") (pin "11") (pinfunction "Y_11") (pintype "bidirectional"))
    )
    (net (code "92") (name "Net-(U2-X1)") (class "Default")
      (node (ref "U2") (pin "1") (pinfunction "X1_1") (pintype "bidirectional"))
      (node (ref "X2") (pin "2") (pinfunction "2_2") (pintype "passive"))
    )
    (net (code "93") (name "Net-(U2-X2)") (class "Default")
      (node (ref "U2") (pin "2") (pinfunction "X2_2") (pintype "bidirectional"))
      (node (ref "X2") (pin "1") (pinfunction "1_1") (pintype "passive"))
    )
    (net (code "94") (name "Net-(U3-SW)") (class "Default")
      (node (ref "L1") (pin "1") (pinfunction "1_1") (pintype "passive"))
      (node (ref "U3") (pin "3") (pinfunction "SW_3") (pintype "bidirectional"))
    )
    (net (code "95") (name "Net-(U3-VFB)") (class "Default")
      (node (ref "C4") (pin "2") (pinfunction "2_2") (pintype "passive"))
      (node (ref "R27") (pin "2") (pinfunction "2_2") (pintype "passive"))
      (node (ref "R3") (pin "1") (pinfunction "1_1") (pintype "passive"))
      (node (ref "U3") (pin "5") (pinfunction "VFB_5") (pintype "input"))
    )
    (net (code "96") (name "Net-(U4-Y)") (class "Default")
      (node (ref "R7") (pin "1") (pinfunction "1_1") (pintype "passive"))
      (node (ref "U4") (pin "4") (pinfunction "Y_4") (pintype "bidirectional"))
    )
    (net (code "97") (name "Net-(U5-ISET)") (class "Default")
      (node (ref "R10") (pin "2") (pinfunction "2_2") (pintype "passive"))
      (node (ref "U5") (pin "2") (pinfunction "ISET_2") (pintype "bidirectional"))
    )
    (net (code "98") (name "unconnected-(J1-Pad1)") (class "Default")
      (node (ref "J1") (pin "1") (pinfunction "1_1") (pintype "bidirectional"))
    )
    (net (code "99") (name "unconnected-(J1-Pad8)") (class "Default")
      (node (ref "J1") (pin "8") (pinfunction "8_8") (pintype "bidirectional"))
    )
    (net (code "100") (name "unconnected-(MICRO_SD-RSV{slash}D1-Pad8)") (class "Default")
      (node (ref "MICRO_SD") (pin "8") (pinfunction "RSV/D1_8") (pintype "bidirectional"))
    )
    (net (code "101") (name "unconnected-(MICRO_SD-RSV{slash}D2-Pad1)") (class "Default")
      (node (ref "MICRO_SD") (pin "1") (pinfunction "RSV/D2_1") (pintype "bidirectional"))
    )
    (net (code "102") (name "unconnected-(SW2-PadSS1)") (class "Default")
      (node (ref "SW2") (pin "SS1") (pinfunction "SS1_SS1") (pintype "bidirectional"))
    )
    (net (code "103") (name "unconnected-(SW2-PadSS2)") (class "Default")
      (node (ref "SW2") (pin "SS2") (pinfunction "SS2_SS2") (pintype "bidirectional"))
    )
    (net (code "104") (name "unconnected-(SW2-PadSS3)") (class "Default")
      (node (ref "SW2") (pin "SS3") (pinfunction "SS3_SS3") (pintype "bidirectional"))
    )
    (net (code "105") (name "unconnected-(SW2-PadSS4)") (class "Default")
      (node (ref "SW2") (pin "SS4") (pinfunction "SS4_SS4") (pintype "bidirectional"))
    )
    (net (code "106") (name "unconnected-(U5-H-PadHEAT)") (class "Default")
      (node (ref "U5") (pin "HEAT") (pinfunction "H_HEAT") (pintype "bidirectional"))
    )
  )
)
